# Wheelbase_Breakout_Board.net
KiCad netlist of a schematic drawn in EasyEDA Pro
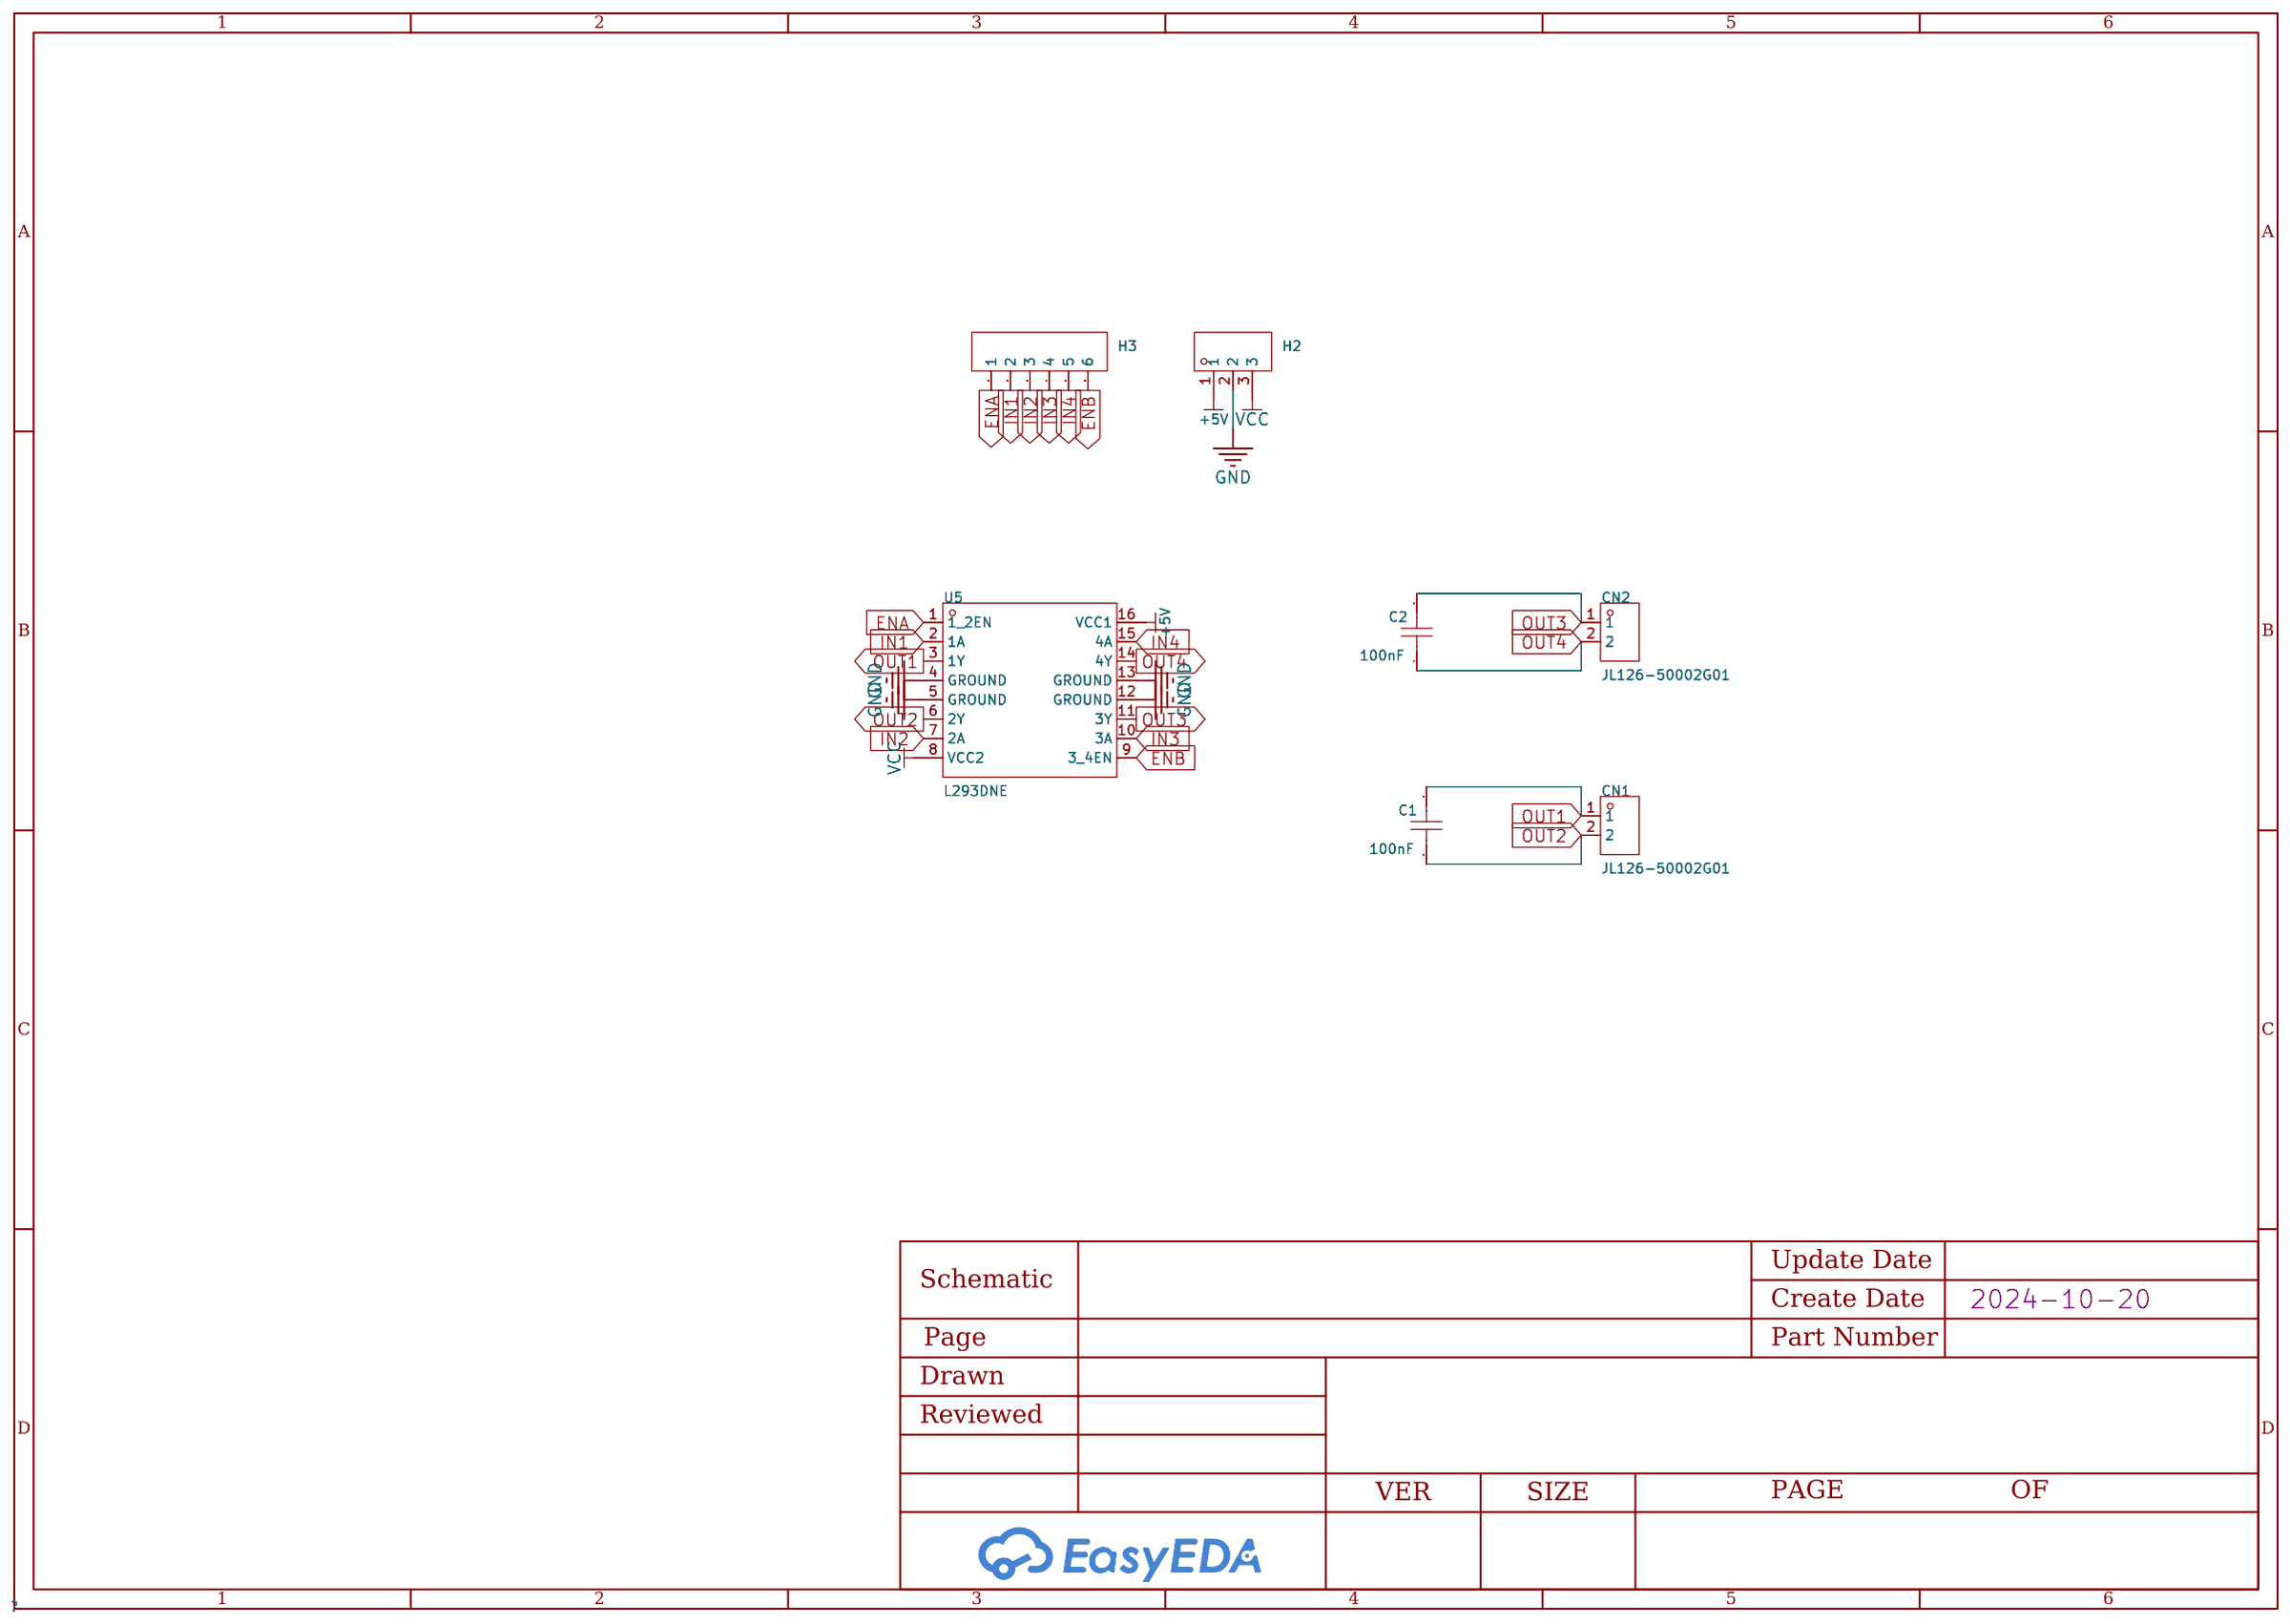
[diagram p0: schematic sheet]

(export (version "E")
  (design (tool "Eeschema 10.0.6"))
  (components
    (comp (ref "C1")
      (value "100nF")
      (footprint "easyedapro:CAP-TH_L6.5-W2.5-P7.50-D0.5")
      (fields
        (field (name "Manufacturer Part") "CD1H104K0DPHR1D000")
        (field (name "Manufacturer") "Dersonic(德尔创)")
      )
      (libsource (lib "easyedapro") (part "CD1H104K0DPHR1D000"))
    )
    (comp (ref "C2")
      (value "100nF")
      (footprint "easyedapro:CAP-TH_L6.5-W2.5-P7.50-D0.5")
      (fields
        (field (name "Manufacturer Part") "CD1H104K0DPHR1D000")
        (field (name "Manufacturer") "Dersonic(德尔创)")
      )
      (libsource (lib "easyedapro") (part "CD1H104K0DPHR1D000"))
    )
    (comp (ref "CN1")
      (value "JL126-50002G01")
      (footprint "easyedapro:CONN-TH_2P-P5.00_JL126-50002G01")
      (fields (field (name "Manufacturer") "JILN(锦凌)"))
      (libsource (lib "easyedapro") (part "JL126-50002G01"))
    )
    (comp (ref "CN2")
      (value "JL126-50002G01")
      (footprint "easyedapro:CONN-TH_2P-P5.00_JL126-50002G01")
      (fields (field (name "Manufacturer") "JILN(锦凌)"))
      (libsource (lib "easyedapro") (part "JL126-50002G01"))
    )
    (comp (ref "H2")
      (value "~")
      (footprint "easyedapro:HDR-TH_3P-P2.54-V-M")
      (libsource (lib "easyedapro") (part "PZ254V-11-03P_C2937625"))
    )
    (comp (ref "H3")
      (value "~")
      (footprint "easyedapro:HDR-TH_6P-P2.54-V-M-1")
      (libsource (lib "easyedapro") (part "Header-Male-2.54_1x6"))
    )
    (comp (ref "U5")
      (value "L293DNE")
      (footprint "easyedapro:DIP-16_L20.0-W6.4-P2.54-LS7.6-BL")
      (fields (field (name "Manufacturer") "TI(德州仪器)"))
      (libsource (lib "easyedapro") (part "L293DNE"))
    )
  )
  (nets
    (net (code "1") (name "+5V") (class "Default")
      (node (ref "H2") (pin "1") (pinfunction "1_1") (pintype "unspecified"))
      (node (ref "U5") (pin "16") (pinfunction "VCC1_16") (pintype "unspecified"))
    )
    (net (code "2") (name "ENA") (class "Default")
      (node (ref "H3") (pin "1") (pinfunction "1_1") (pintype "input"))
      (node (ref "U5") (pin "1") (pinfunction "1_2EN_1") (pintype "unspecified"))
    )
    (net (code "3") (name "ENB") (class "Default")
      (node (ref "H3") (pin "6") (pinfunction "6_6") (pintype "input"))
      (node (ref "U5") (pin "9") (pinfunction "3_4EN_9") (pintype "unspecified"))
    )
    (net (code "4") (name "GND") (class "Default")
      (node (ref "H2") (pin "2") (pinfunction "2_2") (pintype "unspecified"))
      (node (ref "U5") (pin "12") (pinfunction "GROUND_12") (pintype "unspecified"))
      (node (ref "U5") (pin "13") (pinfunction "GROUND_13") (pintype "unspecified"))
      (node (ref "U5") (pin "4") (pinfunction "GROUND_4") (pintype "unspecified"))
      (node (ref "U5") (pin "5") (pinfunction "GROUND_5") (pintype "unspecified"))
    )
    (net (code "5") (name "IN1") (class "Default")
      (node (ref "H3") (pin "2") (pinfunction "2_2") (pintype "input"))
      (node (ref "U5") (pin "2") (pinfunction "1A_2") (pintype "unspecified"))
    )
    (net (code "6") (name "IN2") (class "Default")
      (node (ref "H3") (pin "3") (pinfunction "3_3") (pintype "input"))
      (node (ref "U5") (pin "7") (pinfunction "2A_7") (pintype "unspecified"))
    )
    (net (code "7") (name "IN3") (class "Default")
      (node (ref "H3") (pin "4") (pinfunction "4_4") (pintype "input"))
      (node (ref "U5") (pin "10") (pinfunction "3A_10") (pintype "unspecified"))
    )
    (net (code "8") (name "IN4") (class "Default")
      (node (ref "H3") (pin "5") (pinfunction "5_5") (pintype "input"))
      (node (ref "U5") (pin "15") (pinfunction "4A_15") (pintype "unspecified"))
    )
    (net (code "9") (name "OUT1") (class "Default")
      (node (ref "C1") (pin "1") (pinfunction "1_1") (pintype "unspecified"))
      (node (ref "CN1") (pin "1") (pinfunction "1_1") (pintype "unspecified"))
      (node (ref "U5") (pin "3") (pinfunction "1Y_3") (pintype "unspecified"))
    )
    (net (code "10") (name "OUT2") (class "Default")
      (node (ref "C1") (pin "2") (pinfunction "2_2") (pintype "unspecified"))
      (node (ref "CN1") (pin "2") (pinfunction "2_2") (pintype "unspecified"))
      (node (ref "U5") (pin "6") (pinfunction "2Y_6") (pintype "unspecified"))
    )
    (net (code "11") (name "OUT3") (class "Default")
      (node (ref "C2") (pin "2") (pinfunction "2_2") (pintype "unspecified"))
      (node (ref "CN2") (pin "1") (pinfunction "1_1") (pintype "unspecified"))
      (node (ref "U5") (pin "11") (pinfunction "3Y_11") (pintype "unspecified"))
    )
    (net (code "12") (name "OUT4") (class "Default")
      (node (ref "C2") (pin "1") (pinfunction "1_1") (pintype "unspecified"))
      (node (ref "CN2") (pin "2") (pinfunction "2_2") (pintype "unspecified"))
      (node (ref "U5") (pin "14") (pinfunction "4Y_14") (pintype "unspecified"))
    )
    (net (code "13") (name "VCC") (class "Default")
      (node (ref "H2") (pin "3") (pinfunction "3_3") (pintype "unspecified"))
      (node (ref "U5") (pin "8") (pinfunction "VCC2_8") (pintype "unspecified"))
    )
  )
)
